# RF_FRONTEND.net
KiCad netlist of a schematic drawn in Altium Designer
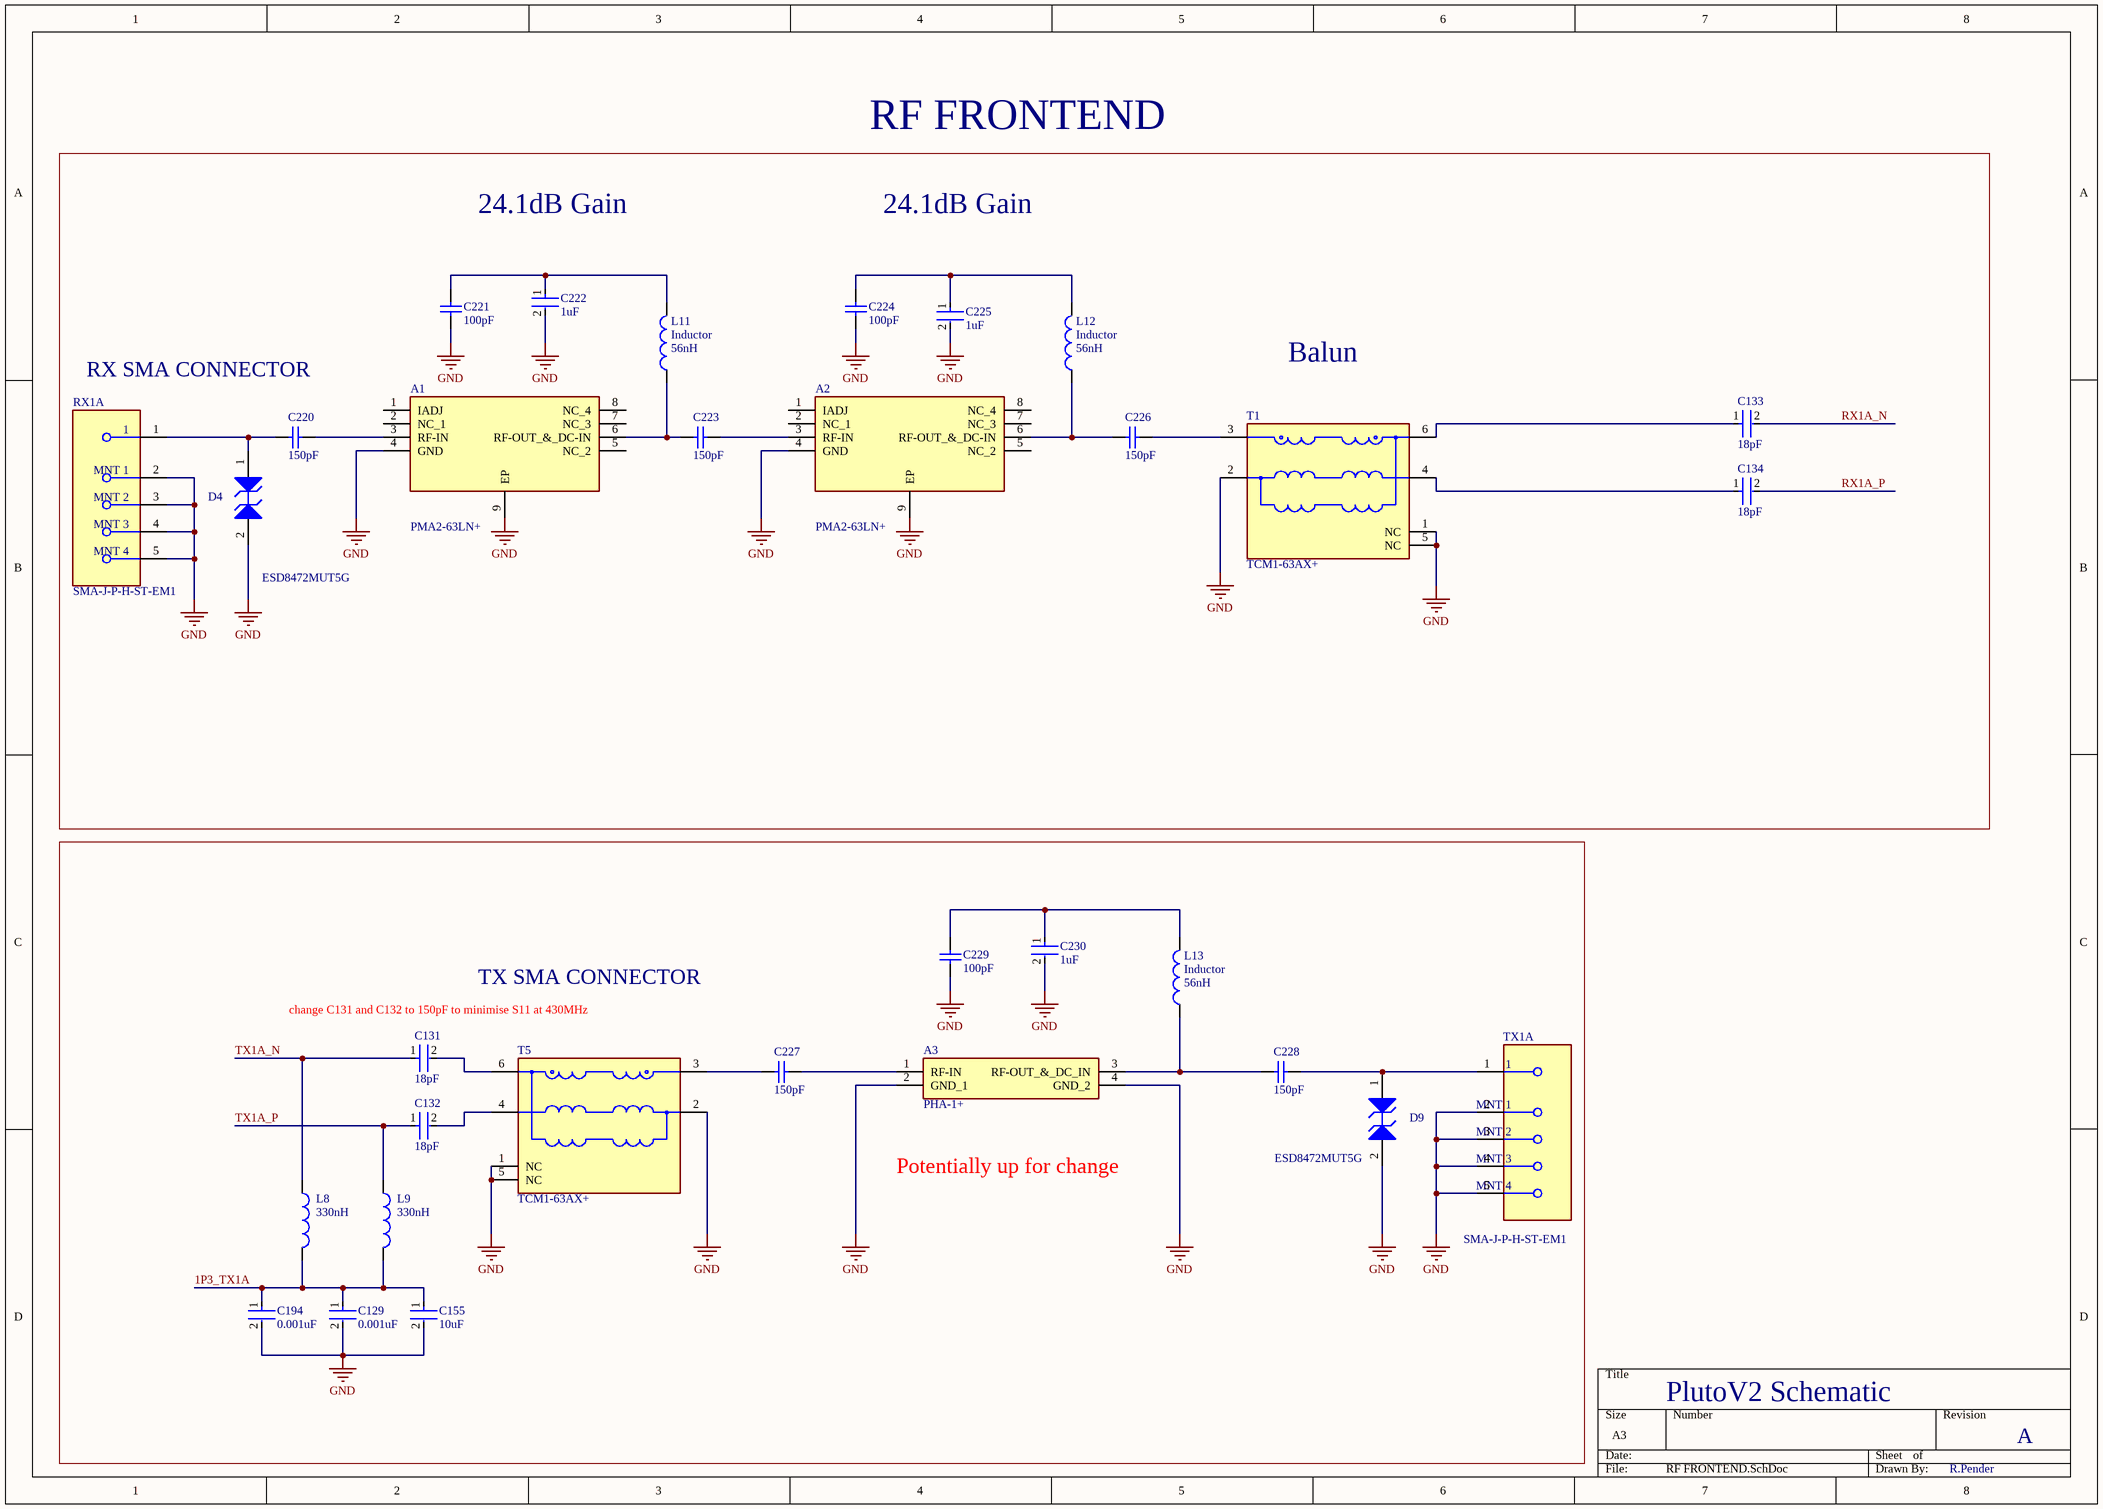
[diagram p0: RF FRONTEND.SchDoc]

(export (version "E")
  (design (tool "Eeschema 10.0.6"))
  (components
    (comp (ref "A1")
      (value "PMA2-63LN+")
      (footprint "SamacSys:SON50P200X200X105-9N")
      (description "Integrated Circuit")
      (libsource (lib "*") (part "PMA2-63LN+"))
    )
    (comp (ref "A2")
      (value "PMA2-63LN+")
      (footprint "SamacSys:SON50P200X200X105-9N")
      (description "Integrated Circuit")
      (libsource (lib "*") (part "PMA2-63LN+"))
    )
    (comp (ref "A3")
      (value "PHA-1+")
      (footprint "SamacSys:GVA63")
      (description "Integrated Circuit")
      (fields (field (name "MANUFACTURER_PART_NUMBER") "PGA-103+"))
      (libsource (lib "*") (part "PGA-103+"))
    )
    (comp (ref "C129")
      (value "0.001uF")
      (footprint "FP-GRM033-0_03-MFG")
      (description "Chip Multilayer Ceramic Capacitors for General Purpose, 0201, 1000pF, X7R, 15%, 10%, 25V")
      (fields (field (name "TOLERANCE") "10%") (field (name "VOLTAGE") "25V"))
      (libsource (lib "Altium Content Vault") (part "b4654b650e69147ec39a6b967a45e02"))
    )
    (comp (ref "C131")
      (value "18pF")
      (footprint "FP-GRM033-0_03-IPC_A")
      (description "Chip Multilayer Ceramic Capacitors for General Purpose, 0201, 18pF, C0G, 30ppm/°C, 5%, 50V")
      (fields (field (name "TOLERANCE") "5%") (field (name "VOLTAGE") "50V"))
      (libsource (lib "Altium Content Vault") (part "b4654b650e69147ec39a6b967a45e02"))
    )
    (comp (ref "C132")
      (value "18pF")
      (footprint "FP-GRM033-0_03-IPC_A")
      (description "Chip Multilayer Ceramic Capacitors for General Purpose, 0201, 18pF, C0G, 30ppm/°C, 5%, 50V")
      (fields (field (name "TOLERANCE") "5%") (field (name "VOLTAGE") "50V"))
      (libsource (lib "Altium Content Vault") (part "b4654b650e69147ec39a6b967a45e02"))
    )
    (comp (ref "C133")
      (value "18pF")
      (footprint "FP-GRM033-0_03-IPC_A")
      (description "Chip Multilayer Ceramic Capacitors for General Purpose, 0201, 18pF, C0G, 30ppm/°C, 5%, 50V")
      (fields (field (name "TOLERANCE") "5%") (field (name "VOLTAGE") "50V"))
      (libsource (lib "Altium Content Vault") (part "b4654b650e69147ec39a6b967a45e02"))
    )
    (comp (ref "C134")
      (value "18pF")
      (footprint "FP-GRM033-0_03-IPC_A")
      (description "Chip Multilayer Ceramic Capacitors for General Purpose, 0201, 18pF, C0G, 30ppm/°C, 5%, 50V")
      (fields (field (name "TOLERANCE") "5%") (field (name "VOLTAGE") "50V"))
      (libsource (lib "Altium Content Vault") (part "b4654b650e69147ec39a6b967a45e02"))
    )
    (comp (ref "C155")
      (value "10uF")
      (footprint "FP-GRM188-0_1-e0_2_0_55-IPC_C")
      (description "Chip Multilayer Ceramic Capacitors for General Purpose, 0603, 10uF, X5R, 15%, 20%, 6.3V")
      (fields (field (name "VOLTAGE") "6.3V") (field (name "TOLERANCE") "20%"))
      (libsource (lib "Altium Content Vault") (part "02cd4be3c70576c341d710602a673aa"))
    )
    (comp (ref "C194")
      (value "0.001uF")
      (footprint "FP-GRM033-0_03-MFG")
      (description "Chip Multilayer Ceramic Capacitors for General Purpose, 0201, 1000pF, X7R, 15%, 10%, 25V")
      (fields (field (name "TOLERANCE") "10%") (field (name "VOLTAGE") "25V"))
      (libsource (lib "Altium Content Vault") (part "b4654b650e69147ec39a6b967a45e02"))
    )
    (comp (ref "C220")
      (value "150pF")
      (footprint "CAPC1005X55X25ML05T10")
      (fields (field (name "MANUFACTURER") "Murata") (field (name "PART NUMBER") "GRM1555C1H151JA01D"))
      (libsource (lib "Altium Content Vault") (part "CAP"))
    )
    (comp (ref "C221")
      (value "100pF")
      (footprint "CAPC1005X55X25ML05T10")
      (fields (field (name "MANUFACTURER") "Murata") (field (name "PART NUMBER") "GRM1555C1H101JA01D"))
      (libsource (lib "Altium Content Vault") (part "CAP"))
    )
    (comp (ref "C222")
      (value "1uF")
      (footprint "FP-GRM155-0_05-IPC_B")
      (description "Chip Multilayer Ceramic Capacitors for General Purpose, 0402, 1.0uF, X5R, 15%, 10%, 25V")
      (fields (field (name "VOLTAGE") "25V") (field (name "TOLERANCE") "10%"))
      (libsource (lib "Altium Content Vault") (part "02cd4be3c70576c341d710602a673aa"))
    )
    (comp (ref "C223")
      (value "150pF")
      (footprint "CAPC1005X55X25ML05T10")
      (fields (field (name "MANUFACTURER") "Murata") (field (name "PART NUMBER") "GRM1555C1H151JA01D"))
      (libsource (lib "Altium Content Vault") (part "CAP"))
    )
    (comp (ref "C224")
      (value "100pF")
      (footprint "CAPC1005X55X25ML05T10")
      (fields (field (name "MANUFACTURER") "Murata") (field (name "PART NUMBER") "GRM1555C1H101JA01D"))
      (libsource (lib "Altium Content Vault") (part "CAP"))
    )
    (comp (ref "C225")
      (value "1uF")
      (footprint "FP-GRM155-0_05-IPC_B")
      (description "Chip Multilayer Ceramic Capacitors for General Purpose, 0402, 1.0uF, X5R, 15%, 10%, 25V")
      (fields (field (name "VOLTAGE") "25V") (field (name "TOLERANCE") "10%"))
      (libsource (lib "Altium Content Vault") (part "02cd4be3c70576c341d710602a673aa"))
    )
    (comp (ref "C226")
      (value "150pF")
      (footprint "CAPC1005X55X25LL05T10")
      (fields (field (name "MANUFACTURER") "Murata") (field (name "PART NUMBER") "GRM1555C1H151JA01D"))
      (libsource (lib "Altium Content Vault") (part "CAP"))
    )
    (comp (ref "C227")
      (value "150pF")
      (footprint "CAPC1005X55X25LL05T10")
      (fields (field (name "MANUFACTURER") "Murata") (field (name "PART NUMBER") "GRM1555C1H151JA01D"))
      (libsource (lib "Altium Content Vault") (part "CAP"))
    )
    (comp (ref "C228")
      (value "150pF")
      (footprint "CAPC1005X55X25LL05T10")
      (fields (field (name "MANUFACTURER") "Murata") (field (name "PART NUMBER") "GRM1555C1H151JA01D"))
      (libsource (lib "Altium Content Vault") (part "CAP"))
    )
    (comp (ref "C229")
      (value "100pF")
      (footprint "CAPC1005X55X25ML05T10")
      (fields (field (name "MANUFACTURER") "Murata") (field (name "PART NUMBER") "GRM1555C1H101JA01D"))
      (libsource (lib "Altium Content Vault") (part "CAP"))
    )
    (comp (ref "C230")
      (value "1uF")
      (footprint "FP-GRM155-0_05-IPC_B")
      (description "Chip Multilayer Ceramic Capacitors for General Purpose, 0402, 1.0uF, X5R, 15%, 10%, 25V")
      (fields (field (name "VOLTAGE") "25V") (field (name "TOLERANCE") "10%"))
      (libsource (lib "Altium Content Vault") (part "02cd4be3c70576c341d710602a673aa"))
    )
    (comp (ref "D4")
      (value "ESD8472MUT5G")
      (footprint "ONSC-X3DFN-2-152AF-01_V")
      (fields (field (name "MANUFACTURER") "On Semiconductor"))
      (libsource (lib "Altium Content Vault") (part "ONSC-A1A2-2"))
    )
    (comp (ref "D9")
      (value "ESD8472MUT5G")
      (footprint "ONSC-X3DFN-2-152AF-01_V")
      (fields (field (name "MANUFACTURER") "On Semiconductor"))
      (libsource (lib "Altium Content Vault") (part "ONSC-A1A2-2"))
    )
    (comp (ref "L8")
      (value "330nH")
      (footprint "INDC2317X140N")
      (description "Inductor")
      (fields (field (name "PUBLISHER") "Altium Limited"))
      (libsource (lib "Miscellaneous Devices") (part "Inductor"))
    )
    (comp (ref "L9")
      (value "330nH")
      (footprint "INDC2317X140N")
      (description "Inductor")
      (fields (field (name "PUBLISHER") "Altium Limited"))
      (libsource (lib "Miscellaneous Devices") (part "Inductor"))
    )
    (comp (ref "L11")
      (value "Inductor")
      (footprint "0402-A")
      (fields (field (name "ALTIUM_VALUE") "56nH") (field (name "PUBLISHER") "Altium Limited"))
      (libsource (lib "Miscellaneous Devices") (part "Inductor"))
    )
    (comp (ref "L12")
      (value "Inductor")
      (footprint "0402-A")
      (fields (field (name "ALTIUM_VALUE") "56nH") (field (name "PUBLISHER") "Altium Limited"))
      (libsource (lib "Miscellaneous Devices") (part "Inductor"))
    )
    (comp (ref "L13")
      (value "Inductor")
      (footprint "0402-A")
      (fields (field (name "ALTIUM_VALUE") "56nH") (field (name "PUBLISHER") "Altium Limited"))
      (libsource (lib "Miscellaneous Devices") (part "Inductor"))
    )
    (comp (ref "RX1A")
      (value "SMA-J-P-H-ST-EM1")
      (footprint "FP-SMA-J-P-H-ST-EM1-MFG")
      (description "CONN SMA JACK STR 50OHM EDGE MNT")
      (libsource (lib "") (part "c65b8a639cdaef1819ea20b5466f8fa_1"))
    )
    (comp (ref "T1")
      (value "TCM1-63AX+")
      (footprint "FP-TCM1-63AX+-MFG")
      (description "1:1 CORE & WIRE Transformer, 10 - 6000 MHz, 50Ω")
      (fields
        (field (name "MANUFACTURER") "Mini-Circuits")
        (field (name "OCTOPART") "https://octopart.com/tcm1-63ax%2B-mini-circuits-107315723")
      )
      (libsource (lib "") (part "572340aedd709dbafee1a1d3331a406_1"))
    )
    (comp (ref "T5")
      (value "TCM1-63AX+")
      (footprint "FP-TCM1-63AX+-MFG")
      (description "1:1 CORE & WIRE Transformer, 10 - 6000 MHz, 50Ω")
      (fields
        (field (name "MANUFACTURER") "Mini-Circuits")
        (field (name "OCTOPART") "https://octopart.com/tcm1-63ax%2B-mini-circuits-107315723")
      )
      (libsource (lib "Altium Content Vault") (part "572340aedd709dbafee1a1d3331a406"))
    )
    (comp (ref "TX1A")
      (value "SMA-J-P-H-ST-EM1")
      (footprint "FP-SMA-J-P-H-ST-EM1-MFG")
      (description "CONN SMA JACK STR 50OHM EDGE MNT")
      (libsource (lib "Altium Content Vault") (part "c65b8a639cdaef1819ea20b5466f8fa"))
    )
  )
  (nets
    (net (code "1") (name "/1P3_TX1A") (class "Default")
      (node (ref "C129") (pin "1") (pinfunction "1_1") (pintype "passive"))
      (node (ref "C155") (pin "1") (pinfunction "1_1") (pintype "passive"))
      (node (ref "C194") (pin "1") (pinfunction "1_1") (pintype "passive"))
      (node (ref "L8") (pin "2") (pinfunction "2_2") (pintype "passive"))
      (node (ref "L9") (pin "2") (pinfunction "2_2") (pintype "passive"))
    )
    (net (code "2") (name "/RX1A_N") (class "Default")
      (node (ref "C133") (pin "2") (pinfunction "2_2") (pintype "passive"))
    )
    (net (code "3") (name "/RX1A_P") (class "Default")
      (node (ref "C134") (pin "2") (pinfunction "2_2") (pintype "passive"))
    )
    (net (code "4") (name "/TX1A_N") (class "Default")
      (node (ref "C131") (pin "1") (pinfunction "1_1") (pintype "passive"))
      (node (ref "L8") (pin "1") (pinfunction "1_1") (pintype "passive"))
    )
    (net (code "5") (name "/TX1A_P") (class "Default")
      (node (ref "C132") (pin "1") (pinfunction "1_1") (pintype "passive"))
      (node (ref "L9") (pin "1") (pinfunction "1_1") (pintype "passive"))
    )
    (net (code "6") (name "GND") (class "Default")
      (node (ref "A1") (pin "4") (pinfunction "GND_4") (pintype "passive"))
      (node (ref "A1") (pin "9") (pinfunction "EP_9") (pintype "passive"))
      (node (ref "A2") (pin "4") (pinfunction "GND_4") (pintype "passive"))
      (node (ref "A2") (pin "9") (pinfunction "EP_9") (pintype "passive"))
      (node (ref "A3") (pin "2") (pinfunction "GND_1_2") (pintype "passive"))
      (node (ref "A3") (pin "4") (pinfunction "GND_2_4") (pintype "passive"))
      (node (ref "C129") (pin "2") (pinfunction "2_2") (pintype "passive"))
      (node (ref "C155") (pin "2") (pinfunction "2_2") (pintype "passive"))
      (node (ref "C194") (pin "2") (pinfunction "2_2") (pintype "passive"))
      (node (ref "C221") (pin "2") (pinfunction "2_2") (pintype "passive"))
      (node (ref "C222") (pin "2") (pinfunction "2_2") (pintype "passive"))
      (node (ref "C224") (pin "2") (pinfunction "2_2") (pintype "passive"))
      (node (ref "C225") (pin "2") (pinfunction "2_2") (pintype "passive"))
      (node (ref "C229") (pin "2") (pinfunction "2_2") (pintype "passive"))
      (node (ref "C230") (pin "2") (pinfunction "2_2") (pintype "passive"))
      (node (ref "D4") (pin "2") (pinfunction "A2_2") (pintype "passive"))
      (node (ref "D9") (pin "2") (pinfunction "A2_2") (pintype "passive"))
      (node (ref "RX1A") (pin "2") (pinfunction "MNT_1_2") (pintype "passive"))
      (node (ref "RX1A") (pin "3") (pinfunction "MNT_2_3") (pintype "passive"))
      (node (ref "RX1A") (pin "4") (pinfunction "MNT_3_4") (pintype "passive"))
      (node (ref "RX1A") (pin "5") (pinfunction "MNT_4_5") (pintype "passive"))
      (node (ref "T1") (pin "1") (pinfunction "NC_1") (pintype "passive"))
      (node (ref "T1") (pin "2") (pinfunction "GND_2") (pintype "passive"))
      (node (ref "T1") (pin "5") (pinfunction "NC_5") (pintype "passive"))
      (node (ref "T5") (pin "1") (pinfunction "NC_1") (pintype "passive"))
      (node (ref "T5") (pin "2") (pinfunction "GND_2") (pintype "passive"))
      (node (ref "T5") (pin "5") (pinfunction "NC_5") (pintype "passive"))
      (node (ref "TX1A") (pin "2") (pinfunction "MNT_1_2") (pintype "passive"))
      (node (ref "TX1A") (pin "3") (pinfunction "MNT_2_3") (pintype "passive"))
      (node (ref "TX1A") (pin "4") (pinfunction "MNT_3_4") (pintype "passive"))
      (node (ref "TX1A") (pin "5") (pinfunction "MNT_4_5") (pintype "passive"))
    )
    (net (code "7") (name "Net-(A1-RF-IN)") (class "Default")
      (node (ref "A1") (pin "3") (pinfunction "RF-IN_3") (pintype "passive"))
      (node (ref "C220") (pin "2") (pinfunction "2_2") (pintype "passive"))
    )
    (net (code "8") (name "Net-(A1-RF-OUT_&_DC-IN)") (class "Default")
      (node (ref "A1") (pin "6") (pinfunction "RF-OUT_&_DC-IN_6") (pintype "passive"))
      (node (ref "C223") (pin "1") (pinfunction "1_1") (pintype "passive"))
      (node (ref "L11") (pin "1") (pinfunction "1_1") (pintype "passive"))
    )
    (net (code "9") (name "Net-(A2-RF-IN)") (class "Default")
      (node (ref "A2") (pin "3") (pinfunction "RF-IN_3") (pintype "passive"))
      (node (ref "C223") (pin "2") (pinfunction "2_2") (pintype "passive"))
    )
    (net (code "10") (name "Net-(A2-RF-OUT_&_DC-IN)") (class "Default")
      (node (ref "A2") (pin "6") (pinfunction "RF-OUT_&_DC-IN_6") (pintype "passive"))
      (node (ref "C226") (pin "1") (pinfunction "1_1") (pintype "passive"))
      (node (ref "L12") (pin "1") (pinfunction "1_1") (pintype "passive"))
    )
    (net (code "11") (name "Net-(A3-RF-IN)") (class "Default")
      (node (ref "A3") (pin "1") (pinfunction "RF-IN_1") (pintype "passive"))
      (node (ref "C227") (pin "2") (pinfunction "2_2") (pintype "passive"))
    )
    (net (code "12") (name "Net-(A3-RF-OUT_&_DC_IN)") (class "Default")
      (node (ref "A3") (pin "3") (pinfunction "RF-OUT_&_DC_IN_3") (pintype "passive"))
      (node (ref "C228") (pin "1") (pinfunction "1_1") (pintype "passive"))
      (node (ref "L13") (pin "1") (pinfunction "1_1") (pintype "passive"))
    )
    (net (code "13") (name "Net-(C221-Pad1)") (class "Default")
      (node (ref "C221") (pin "1") (pinfunction "1_1") (pintype "passive"))
      (node (ref "C222") (pin "1") (pinfunction "1_1") (pintype "passive"))
      (node (ref "L11") (pin "2") (pinfunction "2_2") (pintype "passive"))
    )
    (net (code "14") (name "Net-(C224-Pad1)") (class "Default")
      (node (ref "C224") (pin "1") (pinfunction "1_1") (pintype "passive"))
      (node (ref "C225") (pin "1") (pinfunction "1_1") (pintype "passive"))
      (node (ref "L12") (pin "2") (pinfunction "2_2") (pintype "passive"))
    )
    (net (code "15") (name "Net-(C229-Pad1)") (class "Default")
      (node (ref "C229") (pin "1") (pinfunction "1_1") (pintype "passive"))
      (node (ref "C230") (pin "1") (pinfunction "1_1") (pintype "passive"))
      (node (ref "L13") (pin "2") (pinfunction "2_2") (pintype "passive"))
    )
    (net (code "16") (name "Net-(D4-A1)") (class "Default")
      (node (ref "C220") (pin "1") (pinfunction "1_1") (pintype "passive"))
      (node (ref "D4") (pin "1") (pinfunction "A1_1") (pintype "passive"))
      (node (ref "RX1A") (pin "1") (pinfunction "1_1") (pintype "passive"))
    )
    (net (code "17") (name "Net-(D9-A1)") (class "Default")
      (node (ref "C228") (pin "2") (pinfunction "2_2") (pintype "passive"))
      (node (ref "D9") (pin "1") (pinfunction "A1_1") (pintype "passive"))
      (node (ref "TX1A") (pin "1") (pinfunction "1_1") (pintype "passive"))
    )
    (net (code "18") (name "Net-(T1-PRIMARY_DOT)") (class "Default")
      (node (ref "C226") (pin "2") (pinfunction "2_2") (pintype "passive"))
      (node (ref "T1") (pin "3") (pinfunction "PRIMARY_DOT_3") (pintype "passive"))
    )
    (net (code "19") (name "Net-(T1-SECONDARY)") (class "Default")
      (node (ref "C134") (pin "1") (pinfunction "1_1") (pintype "passive"))
      (node (ref "T1") (pin "4") (pinfunction "SECONDARY_4") (pintype "passive"))
    )
    (net (code "20") (name "Net-(T1-SECONDARY_DOT)") (class "Default")
      (node (ref "C133") (pin "1") (pinfunction "1_1") (pintype "passive"))
      (node (ref "T1") (pin "6") (pinfunction "SECONDARY_DOT_6") (pintype "passive"))
    )
    (net (code "21") (name "Net-(T5-PRIMARY_DOT)") (class "Default")
      (node (ref "C227") (pin "1") (pinfunction "1_1") (pintype "passive"))
      (node (ref "T5") (pin "3") (pinfunction "PRIMARY_DOT_3") (pintype "passive"))
    )
    (net (code "22") (name "Net-(T5-SECONDARY)") (class "Default")
      (node (ref "C132") (pin "2") (pinfunction "2_2") (pintype "passive"))
      (node (ref "T5") (pin "4") (pinfunction "SECONDARY_4") (pintype "passive"))
    )
    (net (code "23") (name "Net-(T5-SECONDARY_DOT)") (class "Default")
      (node (ref "C131") (pin "2") (pinfunction "2_2") (pintype "passive"))
      (node (ref "T5") (pin "6") (pinfunction "SECONDARY_DOT_6") (pintype "passive"))
    )
    (net (code "24") (name "unconnected-(A1-IADJ-Pad1)") (class "Default")
      (node (ref "A1") (pin "1") (pinfunction "IADJ_1") (pintype "passive"))
    )
    (net (code "25") (name "unconnected-(A1-NC_1-Pad2)") (class "Default")
      (node (ref "A1") (pin "2") (pinfunction "NC_1_2") (pintype "passive"))
    )
    (net (code "26") (name "unconnected-(A1-NC_2-Pad5)") (class "Default")
      (node (ref "A1") (pin "5") (pinfunction "NC_2_5") (pintype "passive"))
    )
    (net (code "27") (name "unconnected-(A1-NC_3-Pad7)") (class "Default")
      (node (ref "A1") (pin "7") (pinfunction "NC_3_7") (pintype "passive"))
    )
    (net (code "28") (name "unconnected-(A1-NC_4-Pad8)") (class "Default")
      (node (ref "A1") (pin "8") (pinfunction "NC_4_8") (pintype "passive"))
    )
    (net (code "29") (name "unconnected-(A2-IADJ-Pad1)") (class "Default")
      (node (ref "A2") (pin "1") (pinfunction "IADJ_1") (pintype "passive"))
    )
    (net (code "30") (name "unconnected-(A2-NC_1-Pad2)") (class "Default")
      (node (ref "A2") (pin "2") (pinfunction "NC_1_2") (pintype "passive"))
    )
    (net (code "31") (name "unconnected-(A2-NC_2-Pad5)") (class "Default")
      (node (ref "A2") (pin "5") (pinfunction "NC_2_5") (pintype "passive"))
    )
    (net (code "32") (name "unconnected-(A2-NC_3-Pad7)") (class "Default")
      (node (ref "A2") (pin "7") (pinfunction "NC_3_7") (pintype "passive"))
    )
    (net (code "33") (name "unconnected-(A2-NC_4-Pad8)") (class "Default")
      (node (ref "A2") (pin "8") (pinfunction "NC_4_8") (pintype "passive"))
    )
  )
)
